# NX_Baseboard_-_PCIe_M2_-_CR69Z2.net
KiCad netlist of a schematic drawn in EAGLE
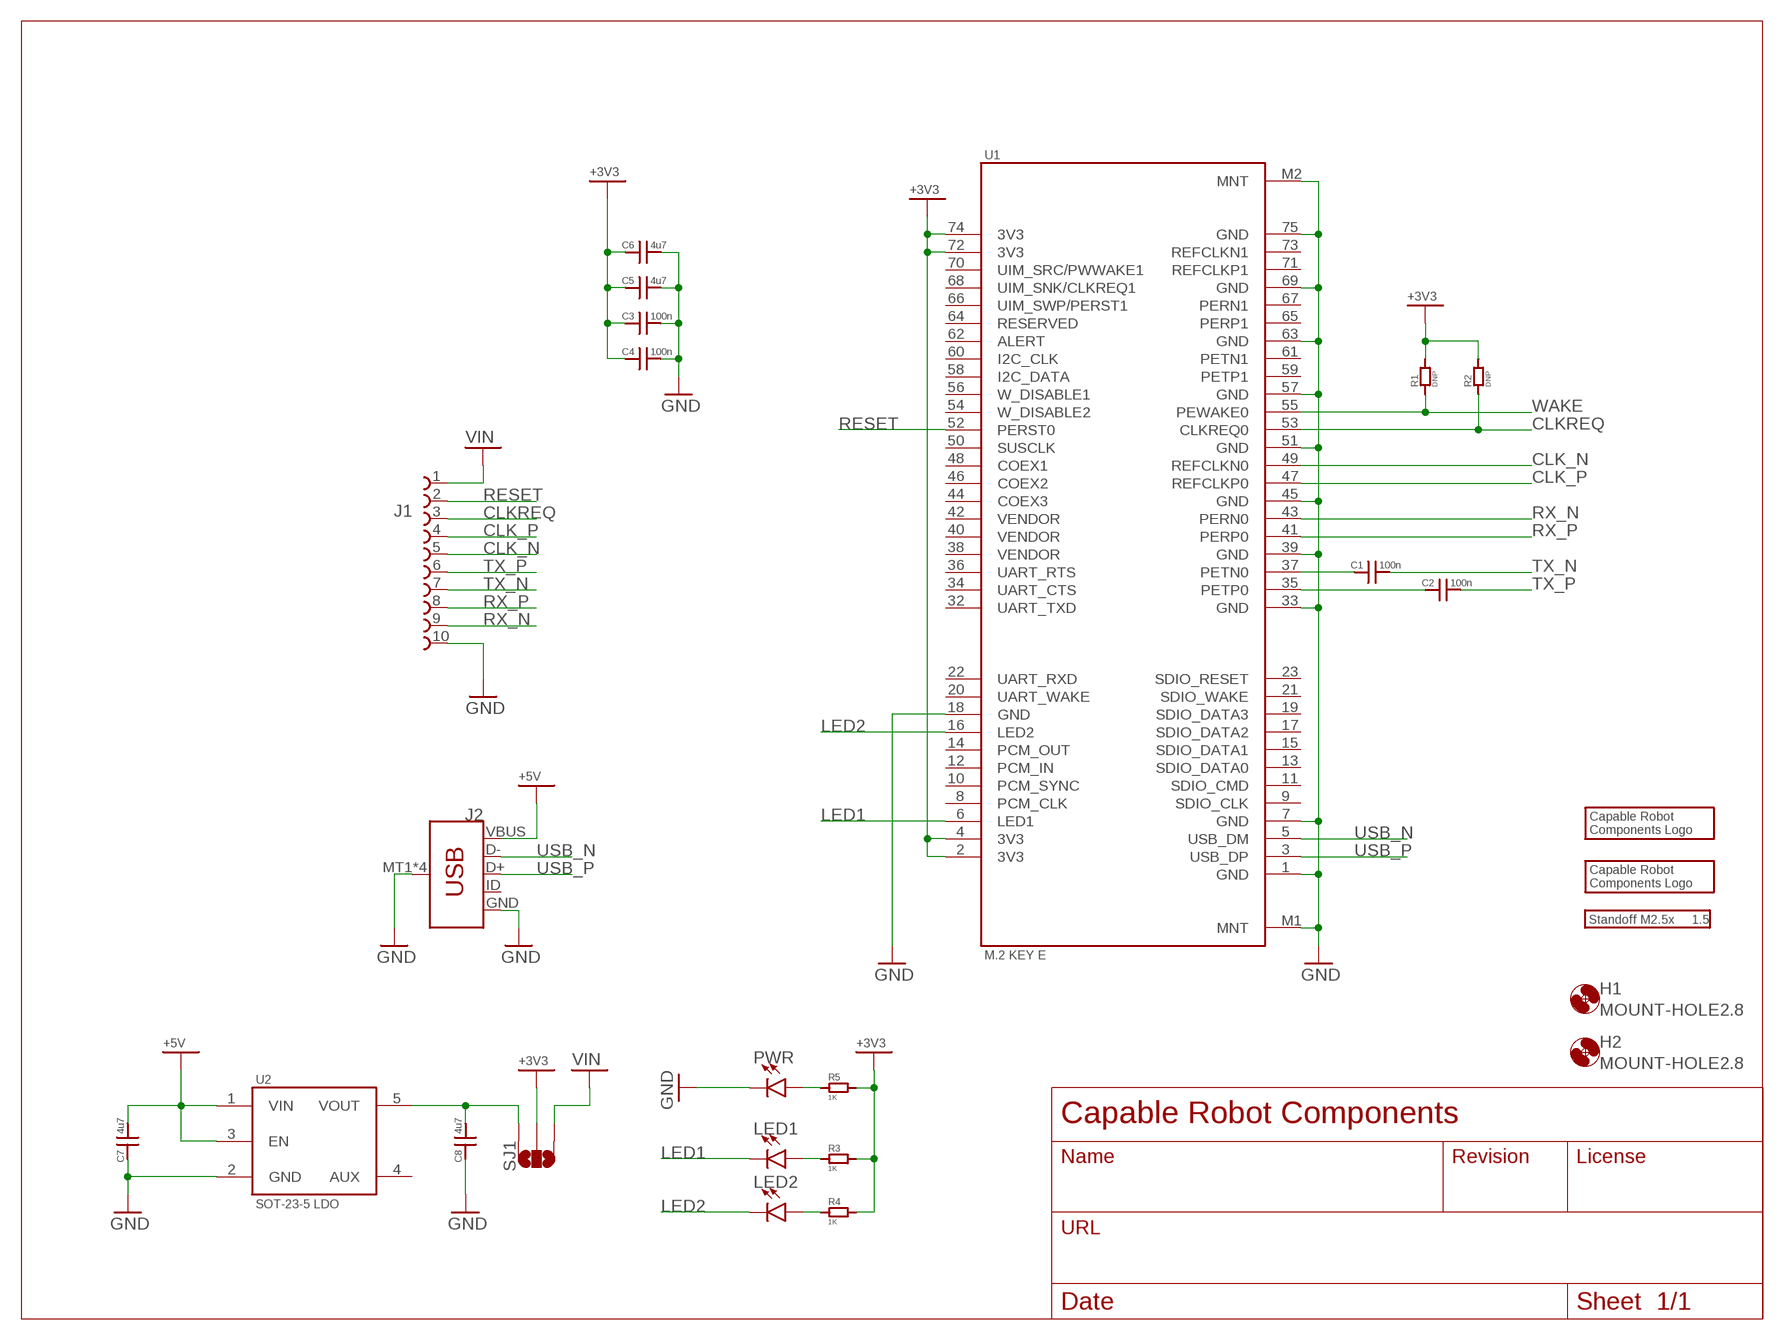
[diagram p0: schematic, sheet 1]

(export (version "E")
  (design (tool "Eeschema 10.0.6"))
  (components
    (comp (ref "C1")
      (value "100n")
      (footprint "eagle-import:0402")
      (libsource (lib "eagle-import") (part "CAP0402"))
    )
    (comp (ref "C2")
      (value "100n")
      (footprint "eagle-import:0402")
      (libsource (lib "eagle-import") (part "CAP0402"))
    )
    (comp (ref "C3")
      (value "100n")
      (footprint "eagle-import:0402")
      (libsource (lib "eagle-import") (part "CAP0402"))
    )
    (comp (ref "C4")
      (value "100n")
      (footprint "eagle-import:0402")
      (libsource (lib "eagle-import") (part "CAP0402"))
    )
    (comp (ref "C5")
      (value "4u7")
      (footprint "eagle-import:0805")
      (libsource (lib "eagle-import") (part "CAP0805"))
    )
    (comp (ref "C6")
      (value "4u7")
      (footprint "eagle-import:0805")
      (libsource (lib "eagle-import") (part "CAP0805"))
    )
    (comp (ref "C7")
      (value "4u7")
      (footprint "eagle-import:0805")
      (libsource (lib "eagle-import") (part "CAP0805"))
    )
    (comp (ref "C8")
      (value "4u7")
      (footprint "eagle-import:0805")
      (libsource (lib "eagle-import") (part "CAP0805"))
    )
    (comp (ref "H1")
      (value "MOUNT-HOLE2.8")
      (footprint "eagle-import:2,8")
      (libsource (lib "eagle-import") (part "MOUNT-HOLE2.8"))
    )
    (comp (ref "H2")
      (value "MOUNT-HOLE2.8")
      (footprint "eagle-import:2,8")
      (libsource (lib "eagle-import") (part "MOUNT-HOLE2.8"))
    )
    (comp (ref "J1")
      (value "68711014522")
      (footprint "eagle-import:68711014522")
      (libsource (lib "eagle-import") (part "68711014522"))
    )
    (comp (ref "J2")
      (value "USB_MICRO-B_SMT")
      (footprint "eagle-import:USB-MICROB")
      (libsource (lib "eagle-import") (part "USB_MICRO-B_SMT"))
    )
    (comp (ref "LED1")
      (value "LED0603")
      (footprint "eagle-import:LED-0603")
      (libsource (lib "eagle-import") (part "LED0603"))
    )
    (comp (ref "LED2")
      (value "LED0603")
      (footprint "eagle-import:LED-0603")
      (libsource (lib "eagle-import") (part "LED0603"))
    )
    (comp (ref "LOGO1")
      (value "CRC-LOGO10SILK")
      (footprint "eagle-import:CRC-LOGO-10-SILK")
      (libsource (lib "eagle-import") (part "CRC-LOGO10SILK"))
    )
    (comp (ref "LOGO2")
      (value "CRC-LOGO5SILK")
      (footprint "eagle-import:CRC-LOGO-5-SILK")
      (libsource (lib "eagle-import") (part "CRC-LOGO5SILK"))
    )
    (comp (ref "M1")
      (value "1.5")
      (footprint "eagle-import:STANDOFF-M25")
      (fields (field (name "MPN") "9774015151R"))
      (libsource (lib "eagle-import") (part "STANDOFF-M25"))
    )
    (comp (ref "PWR")
      (value "LED0603")
      (footprint "eagle-import:LED-0603")
      (libsource (lib "eagle-import") (part "LED0603"))
    )
    (comp (ref "R1")
      (value "DNP")
      (footprint "eagle-import:0603NOCREAM")
      (libsource (lib "eagle-import") (part "RES0603NC"))
    )
    (comp (ref "R2")
      (value "DNP")
      (footprint "eagle-import:0603NOCREAM")
      (libsource (lib "eagle-import") (part "RES0603NC"))
    )
    (comp (ref "R3")
      (value "1K")
      (footprint "eagle-import:0603")
      (libsource (lib "eagle-import") (part "RES0603"))
    )
    (comp (ref "R4")
      (value "1K")
      (footprint "eagle-import:0603")
      (libsource (lib "eagle-import") (part "RES0603"))
    )
    (comp (ref "R5")
      (value "1K")
      (footprint "eagle-import:0603")
      (libsource (lib "eagle-import") (part "RES0603"))
    )
    (comp (ref "SJ1")
      (value "JUMPER-PAD-3-NOYES_SILK")
      (footprint "eagle-import:PAD-JUMPER-3-NO_YES_SILK")
      (libsource (lib "eagle-import") (part "JUMPER-PAD-3-NOYES_SILK"))
    )
    (comp (ref "U1")
      (value "M2-KEYE")
      (footprint "eagle-import:TE-2199119-KEYE")
      (fields (field (name "MPN") "2199119-4"))
      (libsource (lib "eagle-import") (part "M2-KEYE"))
    )
    (comp (ref "U2")
      (value "MIC20XX")
      (footprint "eagle-import:SOT25")
      (libsource (lib "eagle-import") (part "MIC20XX"))
    )
  )
  (nets
    (net (code "1") (name "+3V3") (class "Default")
      (node (ref "C3") (pin "1") (pinfunction "P$1_1") (pintype "bidirectional"))
      (node (ref "C4") (pin "1") (pinfunction "P$1_1") (pintype "bidirectional"))
      (node (ref "C5") (pin "1") (pinfunction "P$1_1") (pintype "bidirectional"))
      (node (ref "C6") (pin "1") (pinfunction "P$1_1") (pintype "bidirectional"))
      (node (ref "R1") (pin "2") (pinfunction "2_2") (pintype "passive"))
      (node (ref "R2") (pin "2") (pinfunction "2_2") (pintype "passive"))
      (node (ref "R3") (pin "2") (pinfunction "2_2") (pintype "passive"))
      (node (ref "R4") (pin "2") (pinfunction "2_2") (pintype "passive"))
      (node (ref "R5") (pin "2") (pinfunction "2_2") (pintype "passive"))
      (node (ref "SJ1") (pin "2") (pinfunction "2_2") (pintype "passive"))
      (node (ref "U1") (pin "2") (pinfunction "3V3_2") (pintype "bidirectional"))
      (node (ref "U1") (pin "4") (pinfunction "3V3_4") (pintype "bidirectional"))
      (node (ref "U1") (pin "72") (pinfunction "3V3_72") (pintype "bidirectional"))
      (node (ref "U1") (pin "74") (pinfunction "3V3_74") (pintype "bidirectional"))
    )
    (net (code "2") (name "+5V") (class "Default")
      (node (ref "C7") (pin "2") (pinfunction "P$2_2") (pintype "bidirectional"))
      (node (ref "J2") (pin "VBUS") (pinfunction "VBUS_VBUS") (pintype "power_in"))
      (node (ref "U2") (pin "1") (pinfunction "VIN_1") (pintype "bidirectional"))
      (node (ref "U2") (pin "3") (pinfunction "EN_3") (pintype "bidirectional"))
    )
    (net (code "3") (name "/CLKREQ") (class "Default")
      (node (ref "J1") (pin "3") (pinfunction "3_3") (pintype "passive"))
      (node (ref "R2") (pin "1") (pinfunction "1_1") (pintype "passive"))
      (node (ref "U1") (pin "53") (pinfunction "CLKREQ0_53") (pintype "bidirectional"))
    )
    (net (code "4") (name "/CLK_N") (class "Default")
      (node (ref "J1") (pin "5") (pinfunction "5_5") (pintype "passive"))
      (node (ref "U1") (pin "49") (pinfunction "REFCLKN0_49") (pintype "bidirectional"))
    )
    (net (code "5") (name "/CLK_P") (class "Default")
      (node (ref "J1") (pin "4") (pinfunction "4_4") (pintype "passive"))
      (node (ref "U1") (pin "47") (pinfunction "REFCLKP0_47") (pintype "bidirectional"))
    )
    (net (code "6") (name "/LED1") (class "Default")
      (node (ref "LED1") (pin "C") (pinfunction "C_C") (pintype "passive"))
      (node (ref "U1") (pin "6") (pinfunction "LED1_6") (pintype "bidirectional"))
    )
    (net (code "7") (name "/LED2") (class "Default")
      (node (ref "LED2") (pin "C") (pinfunction "C_C") (pintype "passive"))
      (node (ref "U1") (pin "16") (pinfunction "LED2_16") (pintype "bidirectional"))
    )
    (net (code "8") (name "/RESET") (class "Default")
      (node (ref "J1") (pin "2") (pinfunction "2_2") (pintype "passive"))
      (node (ref "U1") (pin "52") (pinfunction "PERST0_52") (pintype "bidirectional"))
    )
    (net (code "9") (name "/RX_N") (class "Default")
      (node (ref "J1") (pin "9") (pinfunction "9_9") (pintype "passive"))
      (node (ref "U1") (pin "43") (pinfunction "PERN0_43") (pintype "bidirectional"))
    )
    (net (code "10") (name "/RX_P") (class "Default")
      (node (ref "J1") (pin "8") (pinfunction "8_8") (pintype "passive"))
      (node (ref "U1") (pin "41") (pinfunction "PERP0_41") (pintype "bidirectional"))
    )
    (net (code "11") (name "/TX_N") (class "Default")
      (node (ref "C1") (pin "2") (pinfunction "P$2_2") (pintype "bidirectional"))
      (node (ref "J1") (pin "7") (pinfunction "7_7") (pintype "passive"))
    )
    (net (code "12") (name "/TX_P") (class "Default")
      (node (ref "C2") (pin "2") (pinfunction "P$2_2") (pintype "bidirectional"))
      (node (ref "J1") (pin "6") (pinfunction "6_6") (pintype "passive"))
    )
    (net (code "13") (name "/USB_N") (class "Default")
      (node (ref "J2") (pin "D-") (pinfunction "D-_D-") (pintype "bidirectional"))
      (node (ref "U1") (pin "5") (pinfunction "USB_DM_5") (pintype "bidirectional"))
    )
    (net (code "14") (name "/USB_P") (class "Default")
      (node (ref "J2") (pin "D+") (pinfunction "D+_D+") (pintype "bidirectional"))
      (node (ref "U1") (pin "3") (pinfunction "USB_DP_3") (pintype "bidirectional"))
    )
    (net (code "15") (name "/WAKE") (class "Default")
      (node (ref "R1") (pin "1") (pinfunction "1_1") (pintype "passive"))
      (node (ref "U1") (pin "55") (pinfunction "PEWAKE0_55") (pintype "bidirectional"))
    )
    (net (code "16") (name "GND") (class "Default")
      (node (ref "C3") (pin "2") (pinfunction "P$2_2") (pintype "bidirectional"))
      (node (ref "C4") (pin "2") (pinfunction "P$2_2") (pintype "bidirectional"))
      (node (ref "C5") (pin "2") (pinfunction "P$2_2") (pintype "bidirectional"))
      (node (ref "C6") (pin "2") (pinfunction "P$2_2") (pintype "bidirectional"))
      (node (ref "C7") (pin "1") (pinfunction "P$1_1") (pintype "bidirectional"))
      (node (ref "C8") (pin "1") (pinfunction "P$1_1") (pintype "bidirectional"))
      (node (ref "J1") (pin "10") (pinfunction "10_10") (pintype "passive"))
      (node (ref "J2") (pin "GND") (pinfunction "GND_GND") (pintype "power_in"))
      (node (ref "J2") (pin "MT1") (pinfunction "SHIELD_MT1") (pintype "bidirectional"))
      (node (ref "J2") (pin "MT2") (pinfunction "SHIELD_MT2") (pintype "bidirectional"))
      (node (ref "J2") (pin "P$1") (pinfunction "SHIELD_P$1") (pintype "bidirectional"))
      (node (ref "J2") (pin "P$2") (pinfunction "SHIELD_P$2") (pintype "bidirectional"))
      (node (ref "PWR") (pin "C") (pinfunction "C_C") (pintype "passive"))
      (node (ref "U1") (pin "1") (pinfunction "GND_1") (pintype "bidirectional"))
      (node (ref "U1") (pin "18") (pinfunction "GND_18") (pintype "bidirectional"))
      (node (ref "U1") (pin "33") (pinfunction "GND_33") (pintype "bidirectional"))
      (node (ref "U1") (pin "39") (pinfunction "GND_39") (pintype "bidirectional"))
      (node (ref "U1") (pin "45") (pinfunction "GND_45") (pintype "bidirectional"))
      (node (ref "U1") (pin "51") (pinfunction "GND_51") (pintype "bidirectional"))
      (node (ref "U1") (pin "57") (pinfunction "GND_57") (pintype "bidirectional"))
      (node (ref "U1") (pin "63") (pinfunction "GND_63") (pintype "bidirectional"))
      (node (ref "U1") (pin "69") (pinfunction "GND_69") (pintype "bidirectional"))
      (node (ref "U1") (pin "7") (pinfunction "GND_7") (pintype "bidirectional"))
      (node (ref "U1") (pin "75") (pinfunction "GND_75") (pintype "bidirectional"))
      (node (ref "U1") (pin "M1") (pinfunction "MNT_M1") (pintype "bidirectional"))
      (node (ref "U1") (pin "M2") (pinfunction "MNT_M2") (pintype "bidirectional"))
      (node (ref "U2") (pin "2") (pinfunction "GND_2") (pintype "bidirectional"))
    )
    (net (code "17") (name "Net-(C1-P$1)") (class "Default")
      (node (ref "C1") (pin "1") (pinfunction "P$1_1") (pintype "bidirectional"))
      (node (ref "U1") (pin "37") (pinfunction "PETN0_37") (pintype "bidirectional"))
    )
    (net (code "18") (name "Net-(C2-P$1)") (class "Default")
      (node (ref "C2") (pin "1") (pinfunction "P$1_1") (pintype "bidirectional"))
      (node (ref "U1") (pin "35") (pinfunction "PETP0_35") (pintype "bidirectional"))
    )
    (net (code "19") (name "Net-(C8-P$2)") (class "Default")
      (node (ref "C8") (pin "2") (pinfunction "P$2_2") (pintype "bidirectional"))
      (node (ref "SJ1") (pin "3") (pinfunction "3_3") (pintype "passive"))
      (node (ref "U2") (pin "5") (pinfunction "VOUT_5") (pintype "bidirectional"))
    )
    (net (code "20") (name "Net-(LED1-PadA)") (class "Default")
      (node (ref "LED1") (pin "A") (pinfunction "A_A") (pintype "passive"))
      (node (ref "R3") (pin "1") (pinfunction "1_1") (pintype "passive"))
    )
    (net (code "21") (name "Net-(LED2-PadA)") (class "Default")
      (node (ref "LED2") (pin "A") (pinfunction "A_A") (pintype "passive"))
      (node (ref "R4") (pin "1") (pinfunction "1_1") (pintype "passive"))
    )
    (net (code "22") (name "Net-(PWR-PadA)") (class "Default")
      (node (ref "PWR") (pin "A") (pinfunction "A_A") (pintype "passive"))
      (node (ref "R5") (pin "1") (pinfunction "1_1") (pintype "passive"))
    )
    (net (code "23") (name "VIN") (class "Default")
      (node (ref "J1") (pin "1") (pinfunction "1_1") (pintype "passive"))
      (node (ref "SJ1") (pin "1") (pinfunction "1_1") (pintype "passive"))
    )
    (net (code "24") (name "unconnected-(J2-PadID)") (class "Default")
      (node (ref "J2") (pin "ID") (pinfunction "ID_ID") (pintype "bidirectional"))
    )
    (net (code "25") (name "unconnected-(U1-ALERT-Pad62)") (class "Default")
      (node (ref "U1") (pin "62") (pinfunction "ALERT_62") (pintype "bidirectional"))
    )
    (net (code "26") (name "unconnected-(U1-COEX1-Pad48)") (class "Default")
      (node (ref "U1") (pin "48") (pinfunction "COEX1_48") (pintype "bidirectional"))
    )
    (net (code "27") (name "unconnected-(U1-COEX2-Pad46)") (class "Default")
      (node (ref "U1") (pin "46") (pinfunction "COEX2_46") (pintype "bidirectional"))
    )
    (net (code "28") (name "unconnected-(U1-COEX3-Pad44)") (class "Default")
      (node (ref "U1") (pin "44") (pinfunction "COEX3_44") (pintype "bidirectional"))
    )
    (net (code "29") (name "unconnected-(U1-I2C_CLK-Pad60)") (class "Default")
      (node (ref "U1") (pin "60") (pinfunction "I2C_CLK_60") (pintype "bidirectional"))
    )
    (net (code "30") (name "unconnected-(U1-I2C_DATA-Pad58)") (class "Default")
      (node (ref "U1") (pin "58") (pinfunction "I2C_DATA_58") (pintype "bidirectional"))
    )
    (net (code "31") (name "unconnected-(U1-PCM_CLK-Pad8)") (class "Default")
      (node (ref "U1") (pin "8") (pinfunction "PCM_CLK_8") (pintype "bidirectional"))
    )
    (net (code "32") (name "unconnected-(U1-PCM_IN-Pad12)") (class "Default")
      (node (ref "U1") (pin "12") (pinfunction "PCM_IN_12") (pintype "bidirectional"))
    )
    (net (code "33") (name "unconnected-(U1-PCM_OUT-Pad14)") (class "Default")
      (node (ref "U1") (pin "14") (pinfunction "PCM_OUT_14") (pintype "bidirectional"))
    )
    (net (code "34") (name "unconnected-(U1-PCM_SYNC-Pad10)") (class "Default")
      (node (ref "U1") (pin "10") (pinfunction "PCM_SYNC_10") (pintype "bidirectional"))
    )
    (net (code "35") (name "unconnected-(U1-PERN1-Pad67)") (class "Default")
      (node (ref "U1") (pin "67") (pinfunction "PERN1_67") (pintype "bidirectional"))
    )
    (net (code "36") (name "unconnected-(U1-PERP1-Pad65)") (class "Default")
      (node (ref "U1") (pin "65") (pinfunction "PERP1_65") (pintype "bidirectional"))
    )
    (net (code "37") (name "unconnected-(U1-PETN1-Pad61)") (class "Default")
      (node (ref "U1") (pin "61") (pinfunction "PETN1_61") (pintype "bidirectional"))
    )
    (net (code "38") (name "unconnected-(U1-PETP1-Pad59)") (class "Default")
      (node (ref "U1") (pin "59") (pinfunction "PETP1_59") (pintype "bidirectional"))
    )
    (net (code "39") (name "unconnected-(U1-REFCLKN1-Pad73)") (class "Default")
      (node (ref "U1") (pin "73") (pinfunction "REFCLKN1_73") (pintype "bidirectional"))
    )
    (net (code "40") (name "unconnected-(U1-REFCLKP1-Pad71)") (class "Default")
      (node (ref "U1") (pin "71") (pinfunction "REFCLKP1_71") (pintype "bidirectional"))
    )
    (net (code "41") (name "unconnected-(U1-RESERVED-Pad64)") (class "Default")
      (node (ref "U1") (pin "64") (pinfunction "RESERVED_64") (pintype "bidirectional"))
    )
    (net (code "42") (name "unconnected-(U1-SDIO_CLK-Pad9)") (class "Default")
      (node (ref "U1") (pin "9") (pinfunction "SDIO_CLK_9") (pintype "bidirectional"))
    )
    (net (code "43") (name "unconnected-(U1-SDIO_CMD-Pad11)") (class "Default")
      (node (ref "U1") (pin "11") (pinfunction "SDIO_CMD_11") (pintype "bidirectional"))
    )
    (net (code "44") (name "unconnected-(U1-SDIO_DATA0-Pad13)") (class "Default")
      (node (ref "U1") (pin "13") (pinfunction "SDIO_DATA0_13") (pintype "bidirectional"))
    )
    (net (code "45") (name "unconnected-(U1-SDIO_DATA1-Pad15)") (class "Default")
      (node (ref "U1") (pin "15") (pinfunction "SDIO_DATA1_15") (pintype "bidirectional"))
    )
    (net (code "46") (name "unconnected-(U1-SDIO_DATA2-Pad17)") (class "Default")
      (node (ref "U1") (pin "17") (pinfunction "SDIO_DATA2_17") (pintype "bidirectional"))
    )
    (net (code "47") (name "unconnected-(U1-SDIO_DATA3-Pad19)") (class "Default")
      (node (ref "U1") (pin "19") (pinfunction "SDIO_DATA3_19") (pintype "bidirectional"))
    )
    (net (code "48") (name "unconnected-(U1-SDIO_RESET-Pad23)") (class "Default")
      (node (ref "U1") (pin "23") (pinfunction "SDIO_RESET_23") (pintype "bidirectional"))
    )
    (net (code "49") (name "unconnected-(U1-SDIO_WAKE-Pad21)") (class "Default")
      (node (ref "U1") (pin "21") (pinfunction "SDIO_WAKE_21") (pintype "bidirectional"))
    )
    (net (code "50") (name "unconnected-(U1-SUSCLK-Pad50)") (class "Default")
      (node (ref "U1") (pin "50") (pinfunction "SUSCLK_50") (pintype "bidirectional"))
    )
    (net (code "51") (name "unconnected-(U1-UART_CTS-Pad34)") (class "Default")
      (node (ref "U1") (pin "34") (pinfunction "UART_CTS_34") (pintype "bidirectional"))
    )
    (net (code "52") (name "unconnected-(U1-UART_RTS-Pad36)") (class "Default")
      (node (ref "U1") (pin "36") (pinfunction "UART_RTS_36") (pintype "bidirectional"))
    )
    (net (code "53") (name "unconnected-(U1-UART_RXD-Pad22)") (class "Default")
      (node (ref "U1") (pin "22") (pinfunction "UART_RXD_22") (pintype "bidirectional"))
    )
    (net (code "54") (name "unconnected-(U1-UART_TXD-Pad32)") (class "Default")
      (node (ref "U1") (pin "32") (pinfunction "UART_TXD_32") (pintype "bidirectional"))
    )
    (net (code "55") (name "unconnected-(U1-UART_WAKE-Pad20)") (class "Default")
      (node (ref "U1") (pin "20") (pinfunction "UART_WAKE_20") (pintype "bidirectional"))
    )
    (net (code "56") (name "unconnected-(U1-UIM_SNK{slash}CLKREQ1-Pad68)") (class "Default")
      (node (ref "U1") (pin "68") (pinfunction "UIM_SNK/CLKREQ1_68") (pintype "bidirectional"))
    )
    (net (code "57") (name "unconnected-(U1-UIM_SRC{slash}PWWAKE1-Pad70)") (class "Default")
      (node (ref "U1") (pin "70") (pinfunction "UIM_SRC/PWWAKE1_70") (pintype "bidirectional"))
    )
    (net (code "58") (name "unconnected-(U1-UIM_SWP{slash}PERST1-Pad66)") (class "Default")
      (node (ref "U1") (pin "66") (pinfunction "UIM_SWP/PERST1_66") (pintype "bidirectional"))
    )
    (net (code "59") (name "unconnected-(U1-VENDOR-Pad38)") (class "Default")
      (node (ref "U1") (pin "38") (pinfunction "VENDOR_38") (pintype "bidirectional"))
    )
    (net (code "60") (name "unconnected-(U1-VENDOR-Pad40)") (class "Default")
      (node (ref "U1") (pin "40") (pinfunction "VENDOR_40") (pintype "bidirectional"))
    )
    (net (code "61") (name "unconnected-(U1-VENDOR-Pad42)") (class "Default")
      (node (ref "U1") (pin "42") (pinfunction "VENDOR_42") (pintype "bidirectional"))
    )
    (net (code "62") (name "unconnected-(U1-W_DISABLE1-Pad56)") (class "Default")
      (node (ref "U1") (pin "56") (pinfunction "W_DISABLE1_56") (pintype "bidirectional"))
    )
    (net (code "63") (name "unconnected-(U1-W_DISABLE2-Pad54)") (class "Default")
      (node (ref "U1") (pin "54") (pinfunction "W_DISABLE2_54") (pintype "bidirectional"))
    )
    (net (code "64") (name "unconnected-(U2-AUX-Pad4)") (class "Default")
      (node (ref "U2") (pin "4") (pinfunction "AUX_4") (pintype "bidirectional"))
    )
  )
)
